# Extruder_Stepper_Motor_Driver.net
KiCad netlist of a schematic drawn in Altium Designer
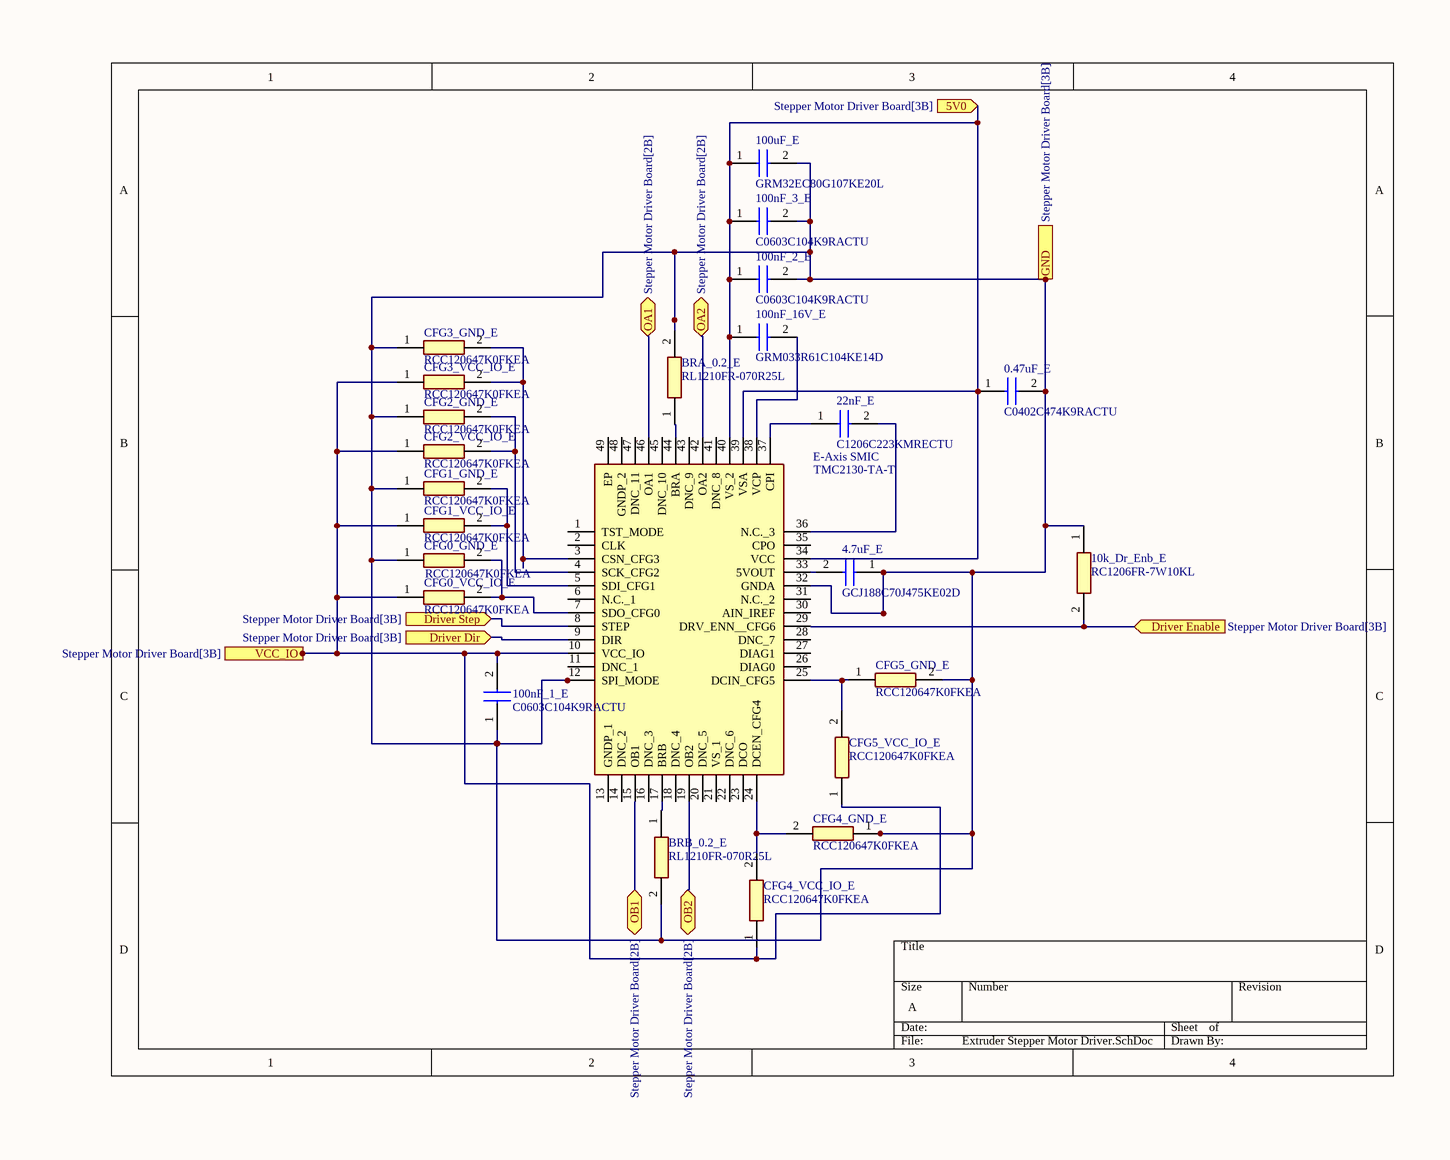
[diagram p0: Extruder Stepper Motor Driver.SchDoc]

(export (version "E")
  (design (tool "Eeschema 10.0.6"))
  (components
    (comp (ref "0.47uF_E")
      (value "C0402C474K9RACTU")
      (footprint "SamacSys:CAPC1005X55N")
      (description "Capacitor")
      (fields (field (name "MOUSER PART NUMBER") "80-C0402C474K9RACTU"))
      (libsource (lib "*") (part "C0402C474K9RACTU"))
    )
    (comp (ref "4.7uF_E")
      (value "GCJ188C70J475KE02D")
      (footprint "SamacSys:CAPC1608X100N")
      (description "Capacitor")
      (fields (field (name "MOUSER PART NUMBER") "81-GCJ188C70J475KE2D"))
      (libsource (lib "*") (part "GCJ188C70J475KE02D"))
    )
    (comp (ref "10k_Dr_Enb_E")
      (value "RC1206FR-7W10KL")
      (footprint "SamacSys:RESC3116X65N")
      (description "Resistor")
      (libsource (lib "*") (part "RC1206FR-7W10KL"))
    )
    (comp (ref "22nF_E")
      (value "C1206C223KMRECTU")
      (footprint "SamacSys:C1206")
      (description "Capacitor")
      (fields (field (name "MOUSER PART NUMBER") "80-C1206C223KMRECTU"))
      (libsource (lib "*") (part "C1206C223KMRECTU"))
    )
    (comp (ref "100nF_1_E")
      (value "C0603C104K9RACTU")
      (footprint "SamacSys:C0603")
      (description "Capacitor")
      (fields (field (name "MOUSER PART NUMBER") "80-C0603C104K9R"))
      (libsource (lib "*") (part "C0603C104K9RACTU"))
    )
    (comp (ref "100nF_2_E")
      (value "C0603C104K9RACTU")
      (footprint "SamacSys:C0603")
      (description "Capacitor")
      (fields (field (name "MOUSER PART NUMBER") "80-C0603C104K9R"))
      (libsource (lib "*") (part "C0603C104K9RACTU"))
    )
    (comp (ref "100nF_3_E")
      (value "C0603C104K9RACTU")
      (footprint "SamacSys:C0603")
      (description "Capacitor")
      (fields (field (name "MOUSER PART NUMBER") "80-C0603C104K9R"))
      (libsource (lib "*") (part "C0603C104K9RACTU"))
    )
    (comp (ref "100nF_16V_E")
      (value "GRM033R61C104KE14D")
      (footprint "SamacSys:CAPC0603X33N")
      (description "Capacitor")
      (fields (field (name "MOUSER PART NUMBER") "81-GRM033R61C104KE4D"))
      (libsource (lib "*") (part "GRM033R61C104KE14D"))
    )
    (comp (ref "100uF_E")
      (value "GRM32EC80G107KE20L")
      (footprint "SamacSys:CAPC3225X270N")
      (description "Capacitor")
      (fields (field (name "MOUSER PART NUMBER") "81-GRM32EC80G107KE0L"))
      (libsource (lib "*") (part "GRM32EC80G107KE20L"))
    )
    (comp (ref "BRA_0.2_E")
      (value "RL1210FR-070R25L")
      (footprint "SamacSys:RESC3126X65N")
      (description "Resistor")
      (fields (field (name "MOUSER PART NUMBER") "603-RL1210FR-070R25L"))
      (libsource (lib "*") (part "RL1210FR-070R25L"))
    )
    (comp (ref "BRB_0.2_E")
      (value "RL1210FR-070R25L")
      (footprint "SamacSys:RESC3126X65N")
      (description "Resistor")
      (fields (field (name "MOUSER PART NUMBER") "603-RL1210FR-070R25L"))
      (libsource (lib "") (part "RL1210FR-070R25L_1"))
    )
    (comp (ref "CFG0_GND_E")
      (value "RCC120647K0FKEA")
      (footprint "SamacSys:RCC1206_e3")
      (description "Resistor")
      (fields (field (name "MOUSER PART NUMBER") "71-RCC120647K0FKEA"))
      (libsource (lib "*") (part "RCC120647K0FKEA"))
    )
    (comp (ref "CFG0_VCC_IO_E")
      (value "RCC120647K0FKEA")
      (footprint "SamacSys:RCC1206_e3")
      (description "Resistor")
      (fields (field (name "MOUSER PART NUMBER") "71-RCC120647K0FKEA"))
      (libsource (lib "*") (part "RCC120647K0FKEA"))
    )
    (comp (ref "CFG1_GND_E")
      (value "RCC120647K0FKEA")
      (footprint "SamacSys:RCC1206_e3")
      (description "Resistor")
      (fields (field (name "MOUSER PART NUMBER") "71-RCC120647K0FKEA"))
      (libsource (lib "*") (part "RCC120647K0FKEA"))
    )
    (comp (ref "CFG1_VCC_IO_E")
      (value "RCC120647K0FKEA")
      (footprint "SamacSys:RCC1206_e3")
      (description "Resistor")
      (fields (field (name "MOUSER PART NUMBER") "71-RCC120647K0FKEA"))
      (libsource (lib "*") (part "RCC120647K0FKEA"))
    )
    (comp (ref "CFG2_GND_E")
      (value "RCC120647K0FKEA")
      (footprint "SamacSys:RCC1206_e3")
      (description "Resistor")
      (fields (field (name "MOUSER PART NUMBER") "71-RCC120647K0FKEA"))
      (libsource (lib "*") (part "RCC120647K0FKEA"))
    )
    (comp (ref "CFG2_VCC_IO_E")
      (value "RCC120647K0FKEA")
      (footprint "SamacSys:RCC1206_e3")
      (description "Resistor")
      (fields (field (name "MOUSER PART NUMBER") "71-RCC120647K0FKEA"))
      (libsource (lib "*") (part "RCC120647K0FKEA"))
    )
    (comp (ref "CFG3_GND_E")
      (value "RCC120647K0FKEA")
      (footprint "SamacSys:RCC1206_e3")
      (description "Resistor")
      (fields (field (name "MOUSER PART NUMBER") "71-RCC120647K0FKEA"))
      (libsource (lib "*") (part "RCC120647K0FKEA"))
    )
    (comp (ref "CFG3_VCC_IO_E")
      (value "RCC120647K0FKEA")
      (footprint "SamacSys:RCC1206_e3")
      (description "Resistor")
      (fields (field (name "MOUSER PART NUMBER") "71-RCC120647K0FKEA"))
      (libsource (lib "*") (part "RCC120647K0FKEA"))
    )
    (comp (ref "CFG4_GND_E")
      (value "RCC120647K0FKEA")
      (footprint "SamacSys:RCC1206_e3")
      (description "Resistor")
      (fields (field (name "MOUSER PART NUMBER") "71-RCC120647K0FKEA"))
      (libsource (lib "") (part "RCC120647K0FKEA_1"))
    )
    (comp (ref "CFG4_VCC_IO_E")
      (value "RCC120647K0FKEA")
      (footprint "SamacSys:RCC1206_e3")
      (description "Resistor")
      (fields (field (name "MOUSER PART NUMBER") "71-RCC120647K0FKEA"))
      (libsource (lib "") (part "RCC120647K0FKEA_2"))
    )
    (comp (ref "CFG5_GND_E")
      (value "RCC120647K0FKEA")
      (footprint "SamacSys:RCC1206_e3")
      (description "Resistor")
      (fields (field (name "MOUSER PART NUMBER") "71-RCC120647K0FKEA"))
      (libsource (lib "*") (part "RCC120647K0FKEA"))
    )
    (comp (ref "CFG5_VCC_IO_E")
      (value "RCC120647K0FKEA")
      (footprint "SamacSys:RCC1206_e3")
      (description "Resistor")
      (fields (field (name "MOUSER PART NUMBER") "71-RCC120647K0FKEA"))
      (libsource (lib "") (part "RCC120647K0FKEA_2"))
    )
    (comp (ref "E-Axis SMIC")
      (value "TMC2130-TA-T")
      (footprint "SamacSys:QFP50P900X900X120-49N")
      (description "Integrated Circuit")
      (fields (field (name "MOUSER PART NUMBER") "700-TMC2130-TA-T"))
      (libsource (lib "*") (part "TMC2130-TA-T"))
    )
  )
  (nets
    (net (code "1") (name "/5V0") (class "Default")
      (node (ref "0.47uF_E") (pin "1") (pinfunction "1_1") (pintype "passive"))
      (node (ref "100nF_16V_E") (pin "1") (pinfunction "1_1") (pintype "passive"))
      (node (ref "100nF_2_E") (pin "1") (pinfunction "1_1") (pintype "passive"))
      (node (ref "100nF_3_E") (pin "1") (pinfunction "1_1") (pintype "passive"))
      (node (ref "100uF_E") (pin "1") (pinfunction "1_1") (pintype "passive"))
      (node (ref "E-Axis SMIC") (pin "34") (pinfunction "VCC_34") (pintype "passive"))
      (node (ref "E-Axis SMIC") (pin "39") (pinfunction "VSA_39") (pintype "passive"))
      (node (ref "E-Axis SMIC") (pin "40") (pinfunction "VS_2_40") (pintype "passive"))
    )
    (net (code "2") (name "/Driver Dir") (class "Default")
      (node (ref "E-Axis SMIC") (pin "9") (pinfunction "DIR_9") (pintype "passive"))
    )
    (net (code "3") (name "/Driver Enable") (class "Default")
      (node (ref "10k_Dr_Enb_E") (pin "2") (pinfunction "2_2") (pintype "passive"))
      (node (ref "E-Axis SMIC") (pin "29") (pinfunction "DRV_ENN__CFG6_29") (pintype "passive"))
    )
    (net (code "4") (name "/Driver Step") (class "Default")
      (node (ref "E-Axis SMIC") (pin "8") (pinfunction "STEP_8") (pintype "passive"))
    )
    (net (code "5") (name "/GND") (class "Default")
      (node (ref "0.47uF_E") (pin "2") (pinfunction "2_2") (pintype "passive"))
      (node (ref "100nF_1_E") (pin "1") (pinfunction "1_1") (pintype "passive"))
      (node (ref "100nF_2_E") (pin "2") (pinfunction "2_2") (pintype "passive"))
      (node (ref "100nF_3_E") (pin "2") (pinfunction "2_2") (pintype "passive"))
      (node (ref "100uF_E") (pin "2") (pinfunction "2_2") (pintype "passive"))
      (node (ref "10k_Dr_Enb_E") (pin "1") (pinfunction "1_1") (pintype "passive"))
      (node (ref "4.7uF_E") (pin "1") (pinfunction "1_1") (pintype "passive"))
      (node (ref "BRA_0.2_E") (pin "2") (pinfunction "2_2") (pintype "passive"))
      (node (ref "BRB_0.2_E") (pin "2") (pinfunction "2_2") (pintype "passive"))
      (node (ref "CFG0_GND_E") (pin "1") (pinfunction "1_1") (pintype "passive"))
      (node (ref "CFG1_GND_E") (pin "1") (pinfunction "1_1") (pintype "passive"))
      (node (ref "CFG2_GND_E") (pin "1") (pinfunction "1_1") (pintype "passive"))
      (node (ref "CFG3_GND_E") (pin "1") (pinfunction "1_1") (pintype "passive"))
      (node (ref "CFG4_GND_E") (pin "1") (pinfunction "1_1") (pintype "passive"))
      (node (ref "CFG5_GND_E") (pin "2") (pinfunction "2_2") (pintype "passive"))
      (node (ref "E-Axis SMIC") (pin "12") (pinfunction "SPI_MODE_12") (pintype "passive"))
      (node (ref "E-Axis SMIC") (pin "32") (pinfunction "GNDA_32") (pintype "passive"))
    )
    (net (code "6") (name "/OA1") (class "Default")
      (node (ref "E-Axis SMIC") (pin "46") (pinfunction "OA1_46") (pintype "passive"))
    )
    (net (code "7") (name "/OA2") (class "Default")
      (node (ref "E-Axis SMIC") (pin "42") (pinfunction "OA2_42") (pintype "passive"))
    )
    (net (code "8") (name "/OB1") (class "Default")
      (node (ref "E-Axis SMIC") (pin "15") (pinfunction "OB1_15") (pintype "passive"))
    )
    (net (code "9") (name "/OB2") (class "Default")
      (node (ref "E-Axis SMIC") (pin "19") (pinfunction "OB2_19") (pintype "passive"))
    )
    (net (code "10") (name "/VCC_IO") (class "Default")
      (node (ref "100nF_1_E") (pin "2") (pinfunction "2_2") (pintype "passive"))
      (node (ref "CFG0_VCC_IO_E") (pin "1") (pinfunction "1_1") (pintype "passive"))
      (node (ref "CFG1_VCC_IO_E") (pin "1") (pinfunction "1_1") (pintype "passive"))
      (node (ref "CFG2_VCC_IO_E") (pin "1") (pinfunction "1_1") (pintype "passive"))
      (node (ref "CFG3_VCC_IO_E") (pin "1") (pinfunction "1_1") (pintype "passive"))
      (node (ref "CFG4_VCC_IO_E") (pin "1") (pinfunction "1_1") (pintype "passive"))
      (node (ref "CFG5_VCC_IO_E") (pin "1") (pinfunction "1_1") (pintype "passive"))
      (node (ref "E-Axis SMIC") (pin "10") (pinfunction "VCC_IO_10") (pintype "passive"))
    )
    (net (code "11") (name "Net-(E-Axis SMIC-5VOUT)") (class "Default")
      (node (ref "4.7uF_E") (pin "2") (pinfunction "2_2") (pintype "passive"))
      (node (ref "E-Axis SMIC") (pin "33") (pinfunction "5VOUT_33") (pintype "passive"))
    )
    (net (code "12") (name "Net-(E-Axis SMIC-BRA)") (class "Default")
      (node (ref "BRA_0.2_E") (pin "1") (pinfunction "1_1") (pintype "passive"))
      (node (ref "E-Axis SMIC") (pin "44") (pinfunction "BRA_44") (pintype "passive"))
    )
    (net (code "13") (name "Net-(E-Axis SMIC-BRB)") (class "Default")
      (node (ref "BRB_0.2_E") (pin "1") (pinfunction "1_1") (pintype "passive"))
      (node (ref "E-Axis SMIC") (pin "17") (pinfunction "BRB_17") (pintype "passive"))
    )
    (net (code "14") (name "Net-(E-Axis SMIC-CPI)") (class "Default")
      (node (ref "22nF_E") (pin "1") (pinfunction "1_1") (pintype "passive"))
      (node (ref "E-Axis SMIC") (pin "37") (pinfunction "CPI_37") (pintype "passive"))
    )
    (net (code "15") (name "Net-(E-Axis SMIC-CSN_CFG3)") (class "Default")
      (node (ref "CFG3_GND_E") (pin "2") (pinfunction "2_2") (pintype "passive"))
      (node (ref "CFG3_VCC_IO_E") (pin "2") (pinfunction "2_2") (pintype "passive"))
      (node (ref "E-Axis SMIC") (pin "3") (pinfunction "CSN_CFG3_3") (pintype "passive"))
    )
    (net (code "16") (name "Net-(E-Axis SMIC-DCEN_CFG4)") (class "Default")
      (node (ref "CFG4_GND_E") (pin "2") (pinfunction "2_2") (pintype "passive"))
      (node (ref "CFG4_VCC_IO_E") (pin "2") (pinfunction "2_2") (pintype "passive"))
      (node (ref "E-Axis SMIC") (pin "24") (pinfunction "DCEN_CFG4_24") (pintype "passive"))
    )
    (net (code "17") (name "Net-(E-Axis SMIC-DCIN_CFG5)") (class "Default")
      (node (ref "CFG5_GND_E") (pin "1") (pinfunction "1_1") (pintype "passive"))
      (node (ref "CFG5_VCC_IO_E") (pin "2") (pinfunction "2_2") (pintype "passive"))
      (node (ref "E-Axis SMIC") (pin "25") (pinfunction "DCIN_CFG5_25") (pintype "passive"))
    )
    (net (code "18") (name "Net-(E-Axis SMIC-N.C._3)") (class "Default")
      (node (ref "22nF_E") (pin "2") (pinfunction "2_2") (pintype "passive"))
      (node (ref "E-Axis SMIC") (pin "36") (pinfunction "N.C._3_36") (pintype "passive"))
    )
    (net (code "19") (name "Net-(E-Axis SMIC-SCK_CFG2)") (class "Default")
      (node (ref "CFG2_GND_E") (pin "2") (pinfunction "2_2") (pintype "passive"))
      (node (ref "CFG2_VCC_IO_E") (pin "2") (pinfunction "2_2") (pintype "passive"))
      (node (ref "E-Axis SMIC") (pin "4") (pinfunction "SCK_CFG2_4") (pintype "passive"))
    )
    (net (code "20") (name "Net-(E-Axis SMIC-SDI_CFG1)") (class "Default")
      (node (ref "CFG1_GND_E") (pin "2") (pinfunction "2_2") (pintype "passive"))
      (node (ref "CFG1_VCC_IO_E") (pin "2") (pinfunction "2_2") (pintype "passive"))
      (node (ref "E-Axis SMIC") (pin "5") (pinfunction "SDI_CFG1_5") (pintype "passive"))
    )
    (net (code "21") (name "Net-(E-Axis SMIC-SDO_CFG0)") (class "Default")
      (node (ref "CFG0_GND_E") (pin "2") (pinfunction "2_2") (pintype "passive"))
      (node (ref "CFG0_VCC_IO_E") (pin "2") (pinfunction "2_2") (pintype "passive"))
      (node (ref "E-Axis SMIC") (pin "7") (pinfunction "SDO_CFG0_7") (pintype "passive"))
    )
    (net (code "22") (name "Net-(E-Axis SMIC-VCP)") (class "Default")
      (node (ref "100nF_16V_E") (pin "2") (pinfunction "2_2") (pintype "passive"))
      (node (ref "E-Axis SMIC") (pin "38") (pinfunction "VCP_38") (pintype "passive"))
    )
    (net (code "23") (name "unconnected-(E-Axis SMIC-AIN_IREF-Pad30)") (class "Default")
      (node (ref "E-Axis SMIC") (pin "30") (pinfunction "AIN_IREF_30") (pintype "passive"))
    )
    (net (code "24") (name "unconnected-(E-Axis SMIC-CLK-Pad2)") (class "Default")
      (node (ref "E-Axis SMIC") (pin "2") (pinfunction "CLK_2") (pintype "passive"))
    )
    (net (code "25") (name "unconnected-(E-Axis SMIC-CPO-Pad35)") (class "Default")
      (node (ref "E-Axis SMIC") (pin "35") (pinfunction "CPO_35") (pintype "passive"))
    )
    (net (code "26") (name "unconnected-(E-Axis SMIC-DCO-Pad23)") (class "Default")
      (node (ref "E-Axis SMIC") (pin "23") (pinfunction "DCO_23") (pintype "passive"))
    )
    (net (code "27") (name "unconnected-(E-Axis SMIC-DIAG0-Pad26)") (class "Default")
      (node (ref "E-Axis SMIC") (pin "26") (pinfunction "DIAG0_26") (pintype "passive"))
    )
    (net (code "28") (name "unconnected-(E-Axis SMIC-DIAG1-Pad27)") (class "Default")
      (node (ref "E-Axis SMIC") (pin "27") (pinfunction "DIAG1_27") (pintype "passive"))
    )
    (net (code "29") (name "unconnected-(E-Axis SMIC-DNC_1-Pad11)") (class "Default")
      (node (ref "E-Axis SMIC") (pin "11") (pinfunction "DNC_1_11") (pintype "passive"))
    )
    (net (code "30") (name "unconnected-(E-Axis SMIC-DNC_2-Pad14)") (class "Default")
      (node (ref "E-Axis SMIC") (pin "14") (pinfunction "DNC_2_14") (pintype "passive"))
    )
    (net (code "31") (name "unconnected-(E-Axis SMIC-DNC_3-Pad16)") (class "Default")
      (node (ref "E-Axis SMIC") (pin "16") (pinfunction "DNC_3_16") (pintype "passive"))
    )
    (net (code "32") (name "unconnected-(E-Axis SMIC-DNC_4-Pad18)") (class "Default")
      (node (ref "E-Axis SMIC") (pin "18") (pinfunction "DNC_4_18") (pintype "passive"))
    )
    (net (code "33") (name "unconnected-(E-Axis SMIC-DNC_5-Pad20)") (class "Default")
      (node (ref "E-Axis SMIC") (pin "20") (pinfunction "DNC_5_20") (pintype "passive"))
    )
    (net (code "34") (name "unconnected-(E-Axis SMIC-DNC_6-Pad22)") (class "Default")
      (node (ref "E-Axis SMIC") (pin "22") (pinfunction "DNC_6_22") (pintype "passive"))
    )
    (net (code "35") (name "unconnected-(E-Axis SMIC-DNC_7-Pad28)") (class "Default")
      (node (ref "E-Axis SMIC") (pin "28") (pinfunction "DNC_7_28") (pintype "passive"))
    )
    (net (code "36") (name "unconnected-(E-Axis SMIC-DNC_8-Pad41)") (class "Default")
      (node (ref "E-Axis SMIC") (pin "41") (pinfunction "DNC_8_41") (pintype "passive"))
    )
    (net (code "37") (name "unconnected-(E-Axis SMIC-DNC_9-Pad43)") (class "Default")
      (node (ref "E-Axis SMIC") (pin "43") (pinfunction "DNC_9_43") (pintype "passive"))
    )
    (net (code "38") (name "unconnected-(E-Axis SMIC-DNC_10-Pad45)") (class "Default")
      (node (ref "E-Axis SMIC") (pin "45") (pinfunction "DNC_10_45") (pintype "passive"))
    )
    (net (code "39") (name "unconnected-(E-Axis SMIC-DNC_11-Pad47)") (class "Default")
      (node (ref "E-Axis SMIC") (pin "47") (pinfunction "DNC_11_47") (pintype "passive"))
    )
    (net (code "40") (name "unconnected-(E-Axis SMIC-EP-Pad49)") (class "Default")
      (node (ref "E-Axis SMIC") (pin "49") (pinfunction "EP_49") (pintype "passive"))
    )
    (net (code "41") (name "unconnected-(E-Axis SMIC-GNDP_1-Pad13)") (class "Default")
      (node (ref "E-Axis SMIC") (pin "13") (pinfunction "GNDP_1_13") (pintype "passive"))
    )
    (net (code "42") (name "unconnected-(E-Axis SMIC-GNDP_2-Pad48)") (class "Default")
      (node (ref "E-Axis SMIC") (pin "48") (pinfunction "GNDP_2_48") (pintype "passive"))
    )
    (net (code "43") (name "unconnected-(E-Axis SMIC-N.C._1-Pad6)") (class "Default")
      (node (ref "E-Axis SMIC") (pin "6") (pinfunction "N.C._1_6") (pintype "passive"))
    )
    (net (code "44") (name "unconnected-(E-Axis SMIC-N.C._2-Pad31)") (class "Default")
      (node (ref "E-Axis SMIC") (pin "31") (pinfunction "N.C._2_31") (pintype "passive"))
    )
    (net (code "45") (name "unconnected-(E-Axis SMIC-TST_MODE-Pad1)") (class "Default")
      (node (ref "E-Axis SMIC") (pin "1") (pinfunction "TST_MODE_1") (pintype "passive"))
    )
    (net (code "46") (name "unconnected-(E-Axis SMIC-VS_1-Pad21)") (class "Default")
      (node (ref "E-Axis SMIC") (pin "21") (pinfunction "VS_1_21") (pintype "passive"))
    )
  )
)
